# WorldClock.net
KiCad netlist of a schematic drawn in EAGLE
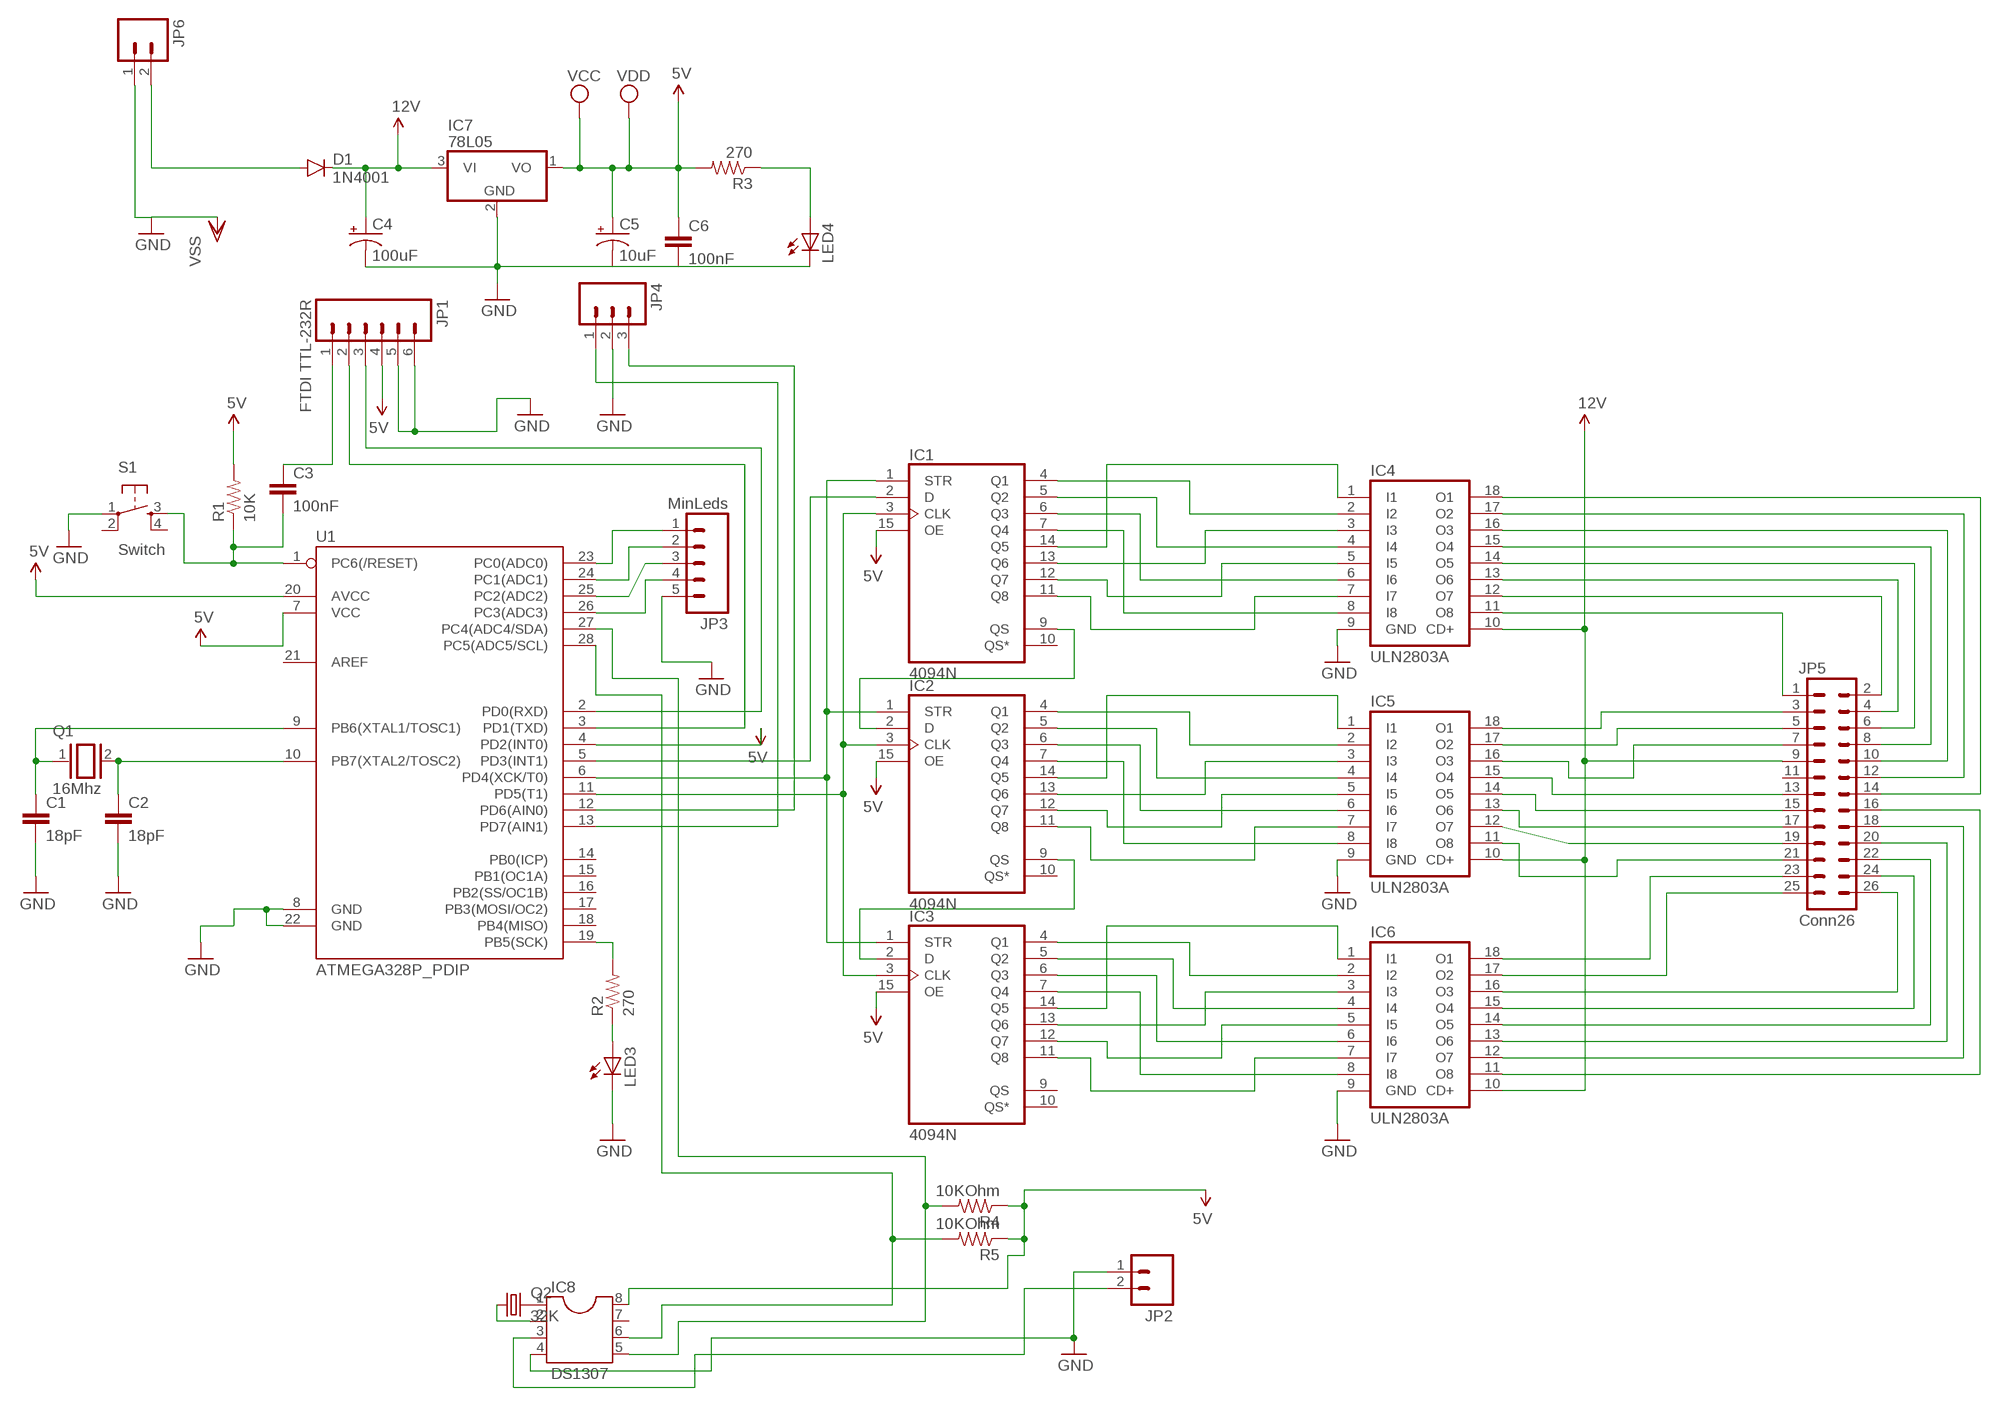
[diagram p0: schematic, sheet 1]

(export (version "E")
  (design (tool "Eeschema 10.0.6"))
  (components
    (comp (ref "C1")
      (value "18pF")
      (footprint "eagle-import:CAP-PTH-SMALL2")
      (libsource (lib "eagle-import") (part "CAPPTH2"))
    )
    (comp (ref "C2")
      (value "18pF")
      (footprint "eagle-import:CAP-PTH-SMALL2")
      (libsource (lib "eagle-import") (part "CAPPTH2"))
    )
    (comp (ref "C3")
      (value "100nF")
      (footprint "eagle-import:CAP-PTH-SMALL2")
      (libsource (lib "eagle-import") (part "CAPPTH2"))
    )
    (comp (ref "C4")
      (value "100uF")
      (footprint "eagle-import:CPOL-RADIAL-100UF-25V")
      (libsource (lib "eagle-import") (part "CAP_POLPTH1"))
    )
    (comp (ref "C5")
      (value "10uF")
      (footprint "eagle-import:CPOL-RADIAL-10UF-25V")
      (libsource (lib "eagle-import") (part "CAP_POLPTH2"))
    )
    (comp (ref "C6")
      (value "100nF")
      (footprint "eagle-import:CAP-PTH-SMALL2")
      (libsource (lib "eagle-import") (part "CAPPTH2"))
    )
    (comp (ref "D1")
      (value "1N4001")
      (footprint "eagle-import:DIODE-1N4148")
      (libsource (lib "eagle-import") (part "DIODE1N4148"))
    )
    (comp (ref "IC1")
      (value "4094N")
      (footprint "eagle-import:DIL16")
      (libsource (lib "eagle-import") (part "4094N"))
    )
    (comp (ref "IC2")
      (value "4094N")
      (footprint "eagle-import:DIL16")
      (libsource (lib "eagle-import") (part "4094N"))
    )
    (comp (ref "IC3")
      (value "4094N")
      (footprint "eagle-import:DIL16")
      (libsource (lib "eagle-import") (part "4094N"))
    )
    (comp (ref "IC4")
      (value "ULN2803A")
      (footprint "eagle-import:DIL18")
      (libsource (lib "eagle-import") (part "ULN2803A"))
    )
    (comp (ref "IC5")
      (value "ULN2803A")
      (footprint "eagle-import:DIL18")
      (libsource (lib "eagle-import") (part "ULN2803A"))
    )
    (comp (ref "IC6")
      (value "ULN2803A")
      (footprint "eagle-import:DIL18")
      (libsource (lib "eagle-import") (part "ULN2803A"))
    )
    (comp (ref "IC7")
      (value "78L05")
      (footprint "eagle-import:TO92")
      (libsource (lib "eagle-import") (part "78ZL12"))
    )
    (comp (ref "IC8")
      (value "DS1307")
      (footprint "eagle-import:SOCKET-08")
      (libsource (lib "eagle-import") (part "DIL8S"))
    )
    (comp (ref "JP1")
      (value "FTDI TTL-232R")
      (footprint "eagle-import:1X06_NO_SILK")
      (libsource (lib "eagle-import") (part "M06NO_SILK_FEMALE_PTH"))
    )
    (comp (ref "JP2")
      (value "M025MM")
      (footprint "eagle-import:SCREWTERMINAL-5MM-2")
      (libsource (lib "eagle-import") (part "M025MM"))
    )
    (comp (ref "JP3")
      (value "MinLeds")
      (footprint "eagle-import:1X05")
      (libsource (lib "eagle-import") (part "M05PTH"))
    )
    (comp (ref "JP4")
      (value "M03-SCREW-5MM")
      (footprint "eagle-import:SCREWTERMINAL-5MM-3")
      (libsource (lib "eagle-import") (part "M03-SCREW-5MM"))
    )
    (comp (ref "JP5")
      (value "Conn26")
      (footprint "eagle-import:2X13")
      (libsource (lib "eagle-import") (part "M13X22X13"))
    )
    (comp (ref "JP6")
      (value "M025MM")
      (footprint "eagle-import:SCREWTERMINAL-5MM-2")
      (libsource (lib "eagle-import") (part "M025MM"))
    )
    (comp (ref "LED3")
      (value "LED5MM")
      (footprint "eagle-import:LED5MM")
      (libsource (lib "eagle-import") (part "LED5MM"))
    )
    (comp (ref "LED4")
      (value "LED5MM")
      (footprint "eagle-import:LED5MM")
      (libsource (lib "eagle-import") (part "LED5MM"))
    )
    (comp (ref "Q1")
      (value "16Mhz")
      (footprint "eagle-import:QS")
      (libsource (lib "eagle-import") (part "XTAL/S"))
    )
    (comp (ref "Q2")
      (value "32K")
      (footprint "eagle-import:TC26V")
      (libsource (lib "eagle-import") (part "CRYSTALTC26V"))
    )
    (comp (ref "R1")
      (value "10K")
      (footprint "eagle-import:AXIAL-0.4")
      (libsource (lib "eagle-import") (part "RESISTORPTH-1/4W"))
    )
    (comp (ref "R2")
      (value "270")
      (footprint "eagle-import:AXIAL-0.4")
      (libsource (lib "eagle-import") (part "RESISTORPTH-1/4W"))
    )
    (comp (ref "R3")
      (value "270")
      (footprint "eagle-import:AXIAL-0.4")
      (libsource (lib "eagle-import") (part "RESISTORPTH-1/4W"))
    )
    (comp (ref "R4")
      (value "10KOhm")
      (footprint "eagle-import:AXIAL-0.4")
      (libsource (lib "eagle-import") (part "RESISTORPTH-1/4W"))
    )
    (comp (ref "R5")
      (value "10KOhm")
      (footprint "eagle-import:AXIAL-0.4")
      (libsource (lib "eagle-import") (part "RESISTORPTH-1/4W"))
    )
    (comp (ref "S1")
      (value "Switch")
      (footprint "eagle-import:TACTILE-PTH")
      (libsource (lib "eagle-import") (part "TAC_SWITCHPTH"))
    )
    (comp (ref "U1")
      (value "ATMEGA328P_PDIP")
      (footprint "eagle-import:DIL28-3")
      (libsource (lib "eagle-import") (part "ATMEGA328P_PDIP"))
    )
  )
  (nets
    (net (code "1") (name "5V") (class "Default")
      (node (ref "C5") (pin "1") (pinfunction "+_1") (pintype "passive"))
      (node (ref "C6") (pin "1") (pinfunction "1_1") (pintype "passive"))
      (node (ref "IC1") (pin "15") (pinfunction "OE_15") (pintype "input"))
      (node (ref "IC2") (pin "15") (pinfunction "OE_15") (pintype "input"))
      (node (ref "IC3") (pin "15") (pinfunction "OE_15") (pintype "input"))
      (node (ref "IC7") (pin "1") (pinfunction "VO_1") (pintype "passive"))
      (node (ref "IC8") (pin "8") (pinfunction "8_8") (pintype "passive"))
      (node (ref "JP1") (pin "4") (pinfunction "4_4") (pintype "passive"))
      (node (ref "R1") (pin "P$2") (pinfunction "2_P$2") (pintype "passive"))
      (node (ref "R3") (pin "P$2") (pinfunction "2_P$2") (pintype "passive"))
      (node (ref "R4") (pin "P$1") (pinfunction "1_P$1") (pintype "passive"))
      (node (ref "R5") (pin "P$1") (pinfunction "1_P$1") (pintype "passive"))
      (node (ref "U1") (pin "20") (pinfunction "AVCC_20") (pintype "bidirectional"))
      (node (ref "U1") (pin "4") (pinfunction "PD2(INT0)_4") (pintype "bidirectional"))
      (node (ref "U1") (pin "7") (pinfunction "VCC_7") (pintype "bidirectional"))
    )
    (net (code "2") (name "12V") (class "Default")
      (node (ref "C4") (pin "1") (pinfunction "+_1") (pintype "passive"))
      (node (ref "D1") (pin "C") (pinfunction "C_C") (pintype "passive"))
      (node (ref "IC4") (pin "10") (pinfunction "CD+_10") (pintype "passive"))
      (node (ref "IC5") (pin "10") (pinfunction "CD+_10") (pintype "passive"))
      (node (ref "IC6") (pin "10") (pinfunction "CD+_10") (pintype "passive"))
      (node (ref "IC7") (pin "3") (pinfunction "VI_3") (pintype "input"))
      (node (ref "JP5") (pin "9") (pinfunction "9_9") (pintype "passive"))
    )
    (net (code "3") (name "GND") (class "Default")
      (node (ref "C1") (pin "2") (pinfunction "2_2") (pintype "passive"))
      (node (ref "C2") (pin "2") (pinfunction "2_2") (pintype "passive"))
      (node (ref "C4") (pin "2") (pinfunction "-_2") (pintype "passive"))
      (node (ref "C5") (pin "2") (pinfunction "-_2") (pintype "passive"))
      (node (ref "C6") (pin "2") (pinfunction "2_2") (pintype "passive"))
      (node (ref "IC4") (pin "9") (pinfunction "GND_9") (pintype "power_in"))
      (node (ref "IC5") (pin "9") (pinfunction "GND_9") (pintype "power_in"))
      (node (ref "IC6") (pin "9") (pinfunction "GND_9") (pintype "power_in"))
      (node (ref "IC7") (pin "2") (pinfunction "GND_2") (pintype "passive"))
      (node (ref "IC8") (pin "4") (pinfunction "4_4") (pintype "passive"))
      (node (ref "JP1") (pin "5") (pinfunction "5_5") (pintype "passive"))
      (node (ref "JP1") (pin "6") (pinfunction "6_6") (pintype "passive"))
      (node (ref "JP2") (pin "1") (pinfunction "1_1") (pintype "passive"))
      (node (ref "JP3") (pin "5") (pinfunction "5_5") (pintype "passive"))
      (node (ref "JP4") (pin "2") (pinfunction "2_2") (pintype "passive"))
      (node (ref "JP6") (pin "1") (pinfunction "1_1") (pintype "passive"))
      (node (ref "LED3") (pin "K") (pinfunction "C_K") (pintype "passive"))
      (node (ref "LED4") (pin "K") (pinfunction "C_K") (pintype "passive"))
      (node (ref "S1") (pin "1") (pinfunction "1_1") (pintype "passive"))
      (node (ref "U1") (pin "22") (pinfunction "GND_22") (pintype "bidirectional"))
      (node (ref "U1") (pin "8") (pinfunction "GND_8") (pintype "bidirectional"))
    )
    (net (code "4") (name "Net-(C3-Pad1)") (class "Default")
      (node (ref "C3") (pin "1") (pinfunction "1_1") (pintype "passive"))
      (node (ref "JP1") (pin "1") (pinfunction "1_1") (pintype "passive"))
    )
    (net (code "5") (name "Net-(D1-PadA)") (class "Default")
      (node (ref "D1") (pin "A") (pinfunction "A_A") (pintype "passive"))
      (node (ref "JP6") (pin "2") (pinfunction "2_2") (pintype "passive"))
    )
    (net (code "6") (name "Net-(IC1A-CLK)") (class "Default")
      (node (ref "IC1") (pin "3") (pinfunction "CLK_3") (pintype "input"))
      (node (ref "IC2") (pin "3") (pinfunction "CLK_3") (pintype "input"))
      (node (ref "IC3") (pin "3") (pinfunction "CLK_3") (pintype "input"))
      (node (ref "U1") (pin "11") (pinfunction "PD5(T1)_11") (pintype "bidirectional"))
    )
    (net (code "7") (name "Net-(IC1A-D)") (class "Default")
      (node (ref "IC1") (pin "2") (pinfunction "D_2") (pintype "input"))
      (node (ref "U1") (pin "5") (pinfunction "PD3(INT1)_5") (pintype "bidirectional"))
    )
    (net (code "8") (name "Net-(IC1A-Q1)") (class "Default")
      (node (ref "IC1") (pin "4") (pinfunction "Q1_4") (pintype "output"))
      (node (ref "IC4") (pin "2") (pinfunction "I2_2") (pintype "input"))
    )
    (net (code "9") (name "Net-(IC1A-Q2)") (class "Default")
      (node (ref "IC1") (pin "5") (pinfunction "Q2_5") (pintype "output"))
      (node (ref "IC4") (pin "4") (pinfunction "I4_4") (pintype "input"))
    )
    (net (code "10") (name "Net-(IC1A-Q3)") (class "Default")
      (node (ref "IC1") (pin "6") (pinfunction "Q3_6") (pintype "output"))
      (node (ref "IC4") (pin "6") (pinfunction "I6_6") (pintype "input"))
    )
    (net (code "11") (name "Net-(IC1A-Q4)") (class "Default")
      (node (ref "IC1") (pin "7") (pinfunction "Q4_7") (pintype "output"))
      (node (ref "IC4") (pin "8") (pinfunction "I8_8") (pintype "input"))
    )
    (net (code "12") (name "Net-(IC1A-Q5)") (class "Default")
      (node (ref "IC1") (pin "14") (pinfunction "Q5_14") (pintype "output"))
      (node (ref "IC4") (pin "1") (pinfunction "I1_1") (pintype "input"))
    )
    (net (code "13") (name "Net-(IC1A-Q6)") (class "Default")
      (node (ref "IC1") (pin "13") (pinfunction "Q6_13") (pintype "output"))
      (node (ref "IC4") (pin "3") (pinfunction "I3_3") (pintype "input"))
    )
    (net (code "14") (name "Net-(IC1A-Q7)") (class "Default")
      (node (ref "IC1") (pin "12") (pinfunction "Q7_12") (pintype "output"))
      (node (ref "IC4") (pin "5") (pinfunction "I5_5") (pintype "input"))
    )
    (net (code "15") (name "Net-(IC1A-Q8)") (class "Default")
      (node (ref "IC1") (pin "11") (pinfunction "Q8_11") (pintype "output"))
      (node (ref "IC4") (pin "7") (pinfunction "I7_7") (pintype "input"))
    )
    (net (code "16") (name "Net-(IC1A-QS)") (class "Default")
      (node (ref "IC1") (pin "9") (pinfunction "QS_9") (pintype "output"))
      (node (ref "IC2") (pin "2") (pinfunction "D_2") (pintype "input"))
    )
    (net (code "17") (name "Net-(IC1A-STR)") (class "Default")
      (node (ref "IC1") (pin "1") (pinfunction "STR_1") (pintype "input"))
      (node (ref "IC2") (pin "1") (pinfunction "STR_1") (pintype "input"))
      (node (ref "IC3") (pin "1") (pinfunction "STR_1") (pintype "input"))
      (node (ref "U1") (pin "6") (pinfunction "PD4(XCK/T0)_6") (pintype "bidirectional"))
    )
    (net (code "18") (name "Net-(IC2A-Q1)") (class "Default")
      (node (ref "IC2") (pin "4") (pinfunction "Q1_4") (pintype "output"))
      (node (ref "IC5") (pin "2") (pinfunction "I2_2") (pintype "input"))
    )
    (net (code "19") (name "Net-(IC2A-Q2)") (class "Default")
      (node (ref "IC2") (pin "5") (pinfunction "Q2_5") (pintype "output"))
      (node (ref "IC5") (pin "4") (pinfunction "I4_4") (pintype "input"))
    )
    (net (code "20") (name "Net-(IC2A-Q3)") (class "Default")
      (node (ref "IC2") (pin "6") (pinfunction "Q3_6") (pintype "output"))
      (node (ref "IC5") (pin "6") (pinfunction "I6_6") (pintype "input"))
    )
    (net (code "21") (name "Net-(IC2A-Q4)") (class "Default")
      (node (ref "IC2") (pin "7") (pinfunction "Q4_7") (pintype "output"))
      (node (ref "IC5") (pin "8") (pinfunction "I8_8") (pintype "input"))
    )
    (net (code "22") (name "Net-(IC2A-Q5)") (class "Default")
      (node (ref "IC2") (pin "14") (pinfunction "Q5_14") (pintype "output"))
      (node (ref "IC5") (pin "1") (pinfunction "I1_1") (pintype "input"))
    )
    (net (code "23") (name "Net-(IC2A-Q6)") (class "Default")
      (node (ref "IC2") (pin "13") (pinfunction "Q6_13") (pintype "output"))
      (node (ref "IC5") (pin "3") (pinfunction "I3_3") (pintype "input"))
    )
    (net (code "24") (name "Net-(IC2A-Q7)") (class "Default")
      (node (ref "IC2") (pin "12") (pinfunction "Q7_12") (pintype "output"))
      (node (ref "IC5") (pin "5") (pinfunction "I5_5") (pintype "input"))
    )
    (net (code "25") (name "Net-(IC2A-Q8)") (class "Default")
      (node (ref "IC2") (pin "11") (pinfunction "Q8_11") (pintype "output"))
      (node (ref "IC5") (pin "7") (pinfunction "I7_7") (pintype "input"))
    )
    (net (code "26") (name "Net-(IC2A-QS)") (class "Default")
      (node (ref "IC2") (pin "9") (pinfunction "QS_9") (pintype "output"))
      (node (ref "IC3") (pin "2") (pinfunction "D_2") (pintype "input"))
    )
    (net (code "27") (name "Net-(IC3A-Q1)") (class "Default")
      (node (ref "IC3") (pin "4") (pinfunction "Q1_4") (pintype "output"))
      (node (ref "IC6") (pin "2") (pinfunction "I2_2") (pintype "input"))
    )
    (net (code "28") (name "Net-(IC3A-Q2)") (class "Default")
      (node (ref "IC3") (pin "5") (pinfunction "Q2_5") (pintype "output"))
      (node (ref "IC6") (pin "4") (pinfunction "I4_4") (pintype "input"))
    )
    (net (code "29") (name "Net-(IC3A-Q3)") (class "Default")
      (node (ref "IC3") (pin "6") (pinfunction "Q3_6") (pintype "output"))
      (node (ref "IC6") (pin "6") (pinfunction "I6_6") (pintype "input"))
    )
    (net (code "30") (name "Net-(IC3A-Q4)") (class "Default")
      (node (ref "IC3") (pin "7") (pinfunction "Q4_7") (pintype "output"))
      (node (ref "IC6") (pin "8") (pinfunction "I8_8") (pintype "input"))
    )
    (net (code "31") (name "Net-(IC3A-Q5)") (class "Default")
      (node (ref "IC3") (pin "14") (pinfunction "Q5_14") (pintype "output"))
      (node (ref "IC6") (pin "1") (pinfunction "I1_1") (pintype "input"))
    )
    (net (code "32") (name "Net-(IC3A-Q6)") (class "Default")
      (node (ref "IC3") (pin "13") (pinfunction "Q6_13") (pintype "output"))
      (node (ref "IC6") (pin "3") (pinfunction "I3_3") (pintype "input"))
    )
    (net (code "33") (name "Net-(IC3A-Q7)") (class "Default")
      (node (ref "IC3") (pin "12") (pinfunction "Q7_12") (pintype "output"))
      (node (ref "IC6") (pin "5") (pinfunction "I5_5") (pintype "input"))
    )
    (net (code "34") (name "Net-(IC3A-Q8)") (class "Default")
      (node (ref "IC3") (pin "11") (pinfunction "Q8_11") (pintype "output"))
      (node (ref "IC6") (pin "7") (pinfunction "I7_7") (pintype "input"))
    )
    (net (code "35") (name "Net-(IC4-O1)") (class "Default")
      (node (ref "IC4") (pin "18") (pinfunction "O1_18") (pintype "open_collector"))
      (node (ref "JP5") (pin "14") (pinfunction "14_14") (pintype "passive"))
    )
    (net (code "36") (name "Net-(IC4-O2)") (class "Default")
      (node (ref "IC4") (pin "17") (pinfunction "O2_17") (pintype "open_collector"))
      (node (ref "JP5") (pin "12") (pinfunction "12_12") (pintype "passive"))
    )
    (net (code "37") (name "Net-(IC4-O3)") (class "Default")
      (node (ref "IC4") (pin "16") (pinfunction "O3_16") (pintype "open_collector"))
      (node (ref "JP5") (pin "10") (pinfunction "10_10") (pintype "passive"))
    )
    (net (code "38") (name "Net-(IC4-O4)") (class "Default")
      (node (ref "IC4") (pin "15") (pinfunction "O4_15") (pintype "open_collector"))
      (node (ref "JP5") (pin "8") (pinfunction "8_8") (pintype "passive"))
    )
    (net (code "39") (name "Net-(IC4-O5)") (class "Default")
      (node (ref "IC4") (pin "14") (pinfunction "O5_14") (pintype "open_collector"))
      (node (ref "JP5") (pin "6") (pinfunction "6_6") (pintype "passive"))
    )
    (net (code "40") (name "Net-(IC4-O6)") (class "Default")
      (node (ref "IC4") (pin "13") (pinfunction "O6_13") (pintype "open_collector"))
      (node (ref "JP5") (pin "4") (pinfunction "4_4") (pintype "passive"))
    )
    (net (code "41") (name "Net-(IC4-O7)") (class "Default")
      (node (ref "IC4") (pin "12") (pinfunction "O7_12") (pintype "open_collector"))
      (node (ref "JP5") (pin "2") (pinfunction "2_2") (pintype "passive"))
    )
    (net (code "42") (name "Net-(IC4-O8)") (class "Default")
      (node (ref "IC4") (pin "11") (pinfunction "O8_11") (pintype "open_collector"))
      (node (ref "JP5") (pin "1") (pinfunction "1_1") (pintype "passive"))
    )
    (net (code "43") (name "Net-(IC5-O1)") (class "Default")
      (node (ref "IC5") (pin "18") (pinfunction "O1_18") (pintype "open_collector"))
      (node (ref "JP5") (pin "3") (pinfunction "3_3") (pintype "passive"))
    )
    (net (code "44") (name "Net-(IC5-O2)") (class "Default")
      (node (ref "IC5") (pin "17") (pinfunction "O2_17") (pintype "open_collector"))
      (node (ref "JP5") (pin "5") (pinfunction "5_5") (pintype "passive"))
    )
    (net (code "45") (name "Net-(IC5-O3)") (class "Default")
      (node (ref "IC5") (pin "16") (pinfunction "O3_16") (pintype "open_collector"))
      (node (ref "JP5") (pin "7") (pinfunction "7_7") (pintype "passive"))
    )
    (net (code "46") (name "Net-(IC5-O4)") (class "Default")
      (node (ref "IC5") (pin "15") (pinfunction "O4_15") (pintype "open_collector"))
      (node (ref "JP5") (pin "13") (pinfunction "13_13") (pintype "passive"))
    )
    (net (code "47") (name "Net-(IC5-O5)") (class "Default")
      (node (ref "IC5") (pin "14") (pinfunction "O5_14") (pintype "open_collector"))
      (node (ref "JP5") (pin "15") (pinfunction "15_15") (pintype "passive"))
    )
    (net (code "48") (name "Net-(IC5-O6)") (class "Default")
      (node (ref "IC5") (pin "13") (pinfunction "O6_13") (pintype "open_collector"))
      (node (ref "JP5") (pin "17") (pinfunction "17_17") (pintype "passive"))
    )
    (net (code "49") (name "Net-(IC5-O7)") (class "Default")
      (node (ref "IC5") (pin "12") (pinfunction "O7_12") (pintype "open_collector"))
      (node (ref "JP5") (pin "19") (pinfunction "19_19") (pintype "passive"))
    )
    (net (code "50") (name "Net-(IC5-O8)") (class "Default")
      (node (ref "IC5") (pin "11") (pinfunction "O8_11") (pintype "open_collector"))
      (node (ref "JP5") (pin "21") (pinfunction "21_21") (pintype "passive"))
    )
    (net (code "51") (name "Net-(IC6-O1)") (class "Default")
      (node (ref "IC6") (pin "18") (pinfunction "O1_18") (pintype "open_collector"))
      (node (ref "JP5") (pin "23") (pinfunction "23_23") (pintype "passive"))
    )
    (net (code "52") (name "Net-(IC6-O2)") (class "Default")
      (node (ref "IC6") (pin "17") (pinfunction "O2_17") (pintype "open_collector"))
      (node (ref "JP5") (pin "25") (pinfunction "25_25") (pintype "passive"))
    )
    (net (code "53") (name "Net-(IC6-O3)") (class "Default")
      (node (ref "IC6") (pin "16") (pinfunction "O3_16") (pintype "open_collector"))
      (node (ref "JP5") (pin "26") (pinfunction "26_26") (pintype "passive"))
    )
    (net (code "54") (name "Net-(IC6-O4)") (class "Default")
      (node (ref "IC6") (pin "15") (pinfunction "O4_15") (pintype "open_collector"))
      (node (ref "JP5") (pin "24") (pinfunction "24_24") (pintype "passive"))
    )
    (net (code "55") (name "Net-(IC6-O5)") (class "Default")
      (node (ref "IC6") (pin "14") (pinfunction "O5_14") (pintype "open_collector"))
      (node (ref "JP5") (pin "22") (pinfunction "22_22") (pintype "passive"))
    )
    (net (code "56") (name "Net-(IC6-O6)") (class "Default")
      (node (ref "IC6") (pin "13") (pinfunction "O6_13") (pintype "open_collector"))
      (node (ref "JP5") (pin "20") (pinfunction "20_20") (pintype "passive"))
    )
    (net (code "57") (name "Net-(IC6-O7)") (class "Default")
      (node (ref "IC6") (pin "12") (pinfunction "O7_12") (pintype "open_collector"))
      (node (ref "JP5") (pin "18") (pinfunction "18_18") (pintype "passive"))
    )
    (net (code "58") (name "Net-(IC6-O8)") (class "Default")
      (node (ref "IC6") (pin "11") (pinfunction "O8_11") (pintype "open_collector"))
      (node (ref "JP5") (pin "16") (pinfunction "16_16") (pintype "passive"))
    )
    (net (code "59") (name "Net-(IC8-Pad1)") (class "Default")
      (node (ref "IC8") (pin "1") (pinfunction "1_1") (pintype "passive"))
      (node (ref "Q2") (pin "2") (pinfunction "2_2") (pintype "passive"))
    )
    (net (code "60") (name "Net-(IC8-Pad2)") (class "Default")
      (node (ref "IC8") (pin "2") (pinfunction "2_2") (pintype "passive"))
      (node (ref "Q2") (pin "1") (pinfunction "1_1") (pintype "passive"))
    )
    (net (code "61") (name "Net-(IC8-Pad3)") (class "Default")
      (node (ref "IC8") (pin "3") (pinfunction "3_3") (pintype "passive"))
      (node (ref "JP2") (pin "2") (pinfunction "2_2") (pintype "passive"))
    )
    (net (code "62") (name "Net-(R1-1)") (class "Default")
      (node (ref "C3") (pin "2") (pinfunction "2_2") (pintype "passive"))
      (node (ref "R1") (pin "P$1") (pinfunction "1_P$1") (pintype "passive"))
      (node (ref "S1") (pin "3") (pinfunction "3_3") (pintype "passive"))
      (node (ref "U1") (pin "1") (pinfunction "PC6(/RESET)_1") (pintype "bidirectional"))
    )
    (net (code "63") (name "Net-(R2-1)") (class "Default")
      (node (ref "LED3") (pin "A") (pinfunction "A_A") (pintype "passive"))
      (node (ref "R2") (pin "P$1") (pinfunction "1_P$1") (pintype "passive"))
    )
    (net (code "64") (name "Net-(R2-2)") (class "Default")
      (node (ref "R2") (pin "P$2") (pinfunction "2_P$2") (pintype "passive"))
      (node (ref "U1") (pin "19") (pinfunction "PB5(SCK)_19") (pintype "bidirectional"))
    )
    (net (code "65") (name "Net-(R3-1)") (class "Default")
      (node (ref "LED4") (pin "A") (pinfunction "A_A") (pintype "passive"))
      (node (ref "R3") (pin "P$1") (pinfunction "1_P$1") (pintype "passive"))
    )
    (net (code "66") (name "Net-(R4-2)") (class "Default")
      (node (ref "IC8") (pin "5") (pinfunction "5_5") (pintype "passive"))
      (node (ref "R4") (pin "P$2") (pinfunction "2_P$2") (pintype "passive"))
      (node (ref "U1") (pin "27") (pinfunction "PC4(ADC4/SDA)_27") (pintype "bidirectional"))
    )
    (net (code "67") (name "Net-(R5-2)") (class "Default")
      (node (ref "IC8") (pin "6") (pinfunction "6_6") (pintype "passive"))
      (node (ref "R5") (pin "P$2") (pinfunction "2_P$2") (pintype "passive"))
      (node (ref "U1") (pin "28") (pinfunction "PC5(ADC5/SCL)_28") (pintype "bidirectional"))
    )
    (net (code "68") (name "Net-(U1-PB6(XTAL1{slash}TOSC1))") (class "Default")
      (node (ref "C1") (pin "1") (pinfunction "1_1") (pintype "passive"))
      (node (ref "Q1") (pin "1") (pinfunction "1_1") (pintype "passive"))
      (node (ref "U1") (pin "9") (pinfunction "PB6(XTAL1/TOSC1)_9") (pintype "bidirectional"))
    )
    (net (code "69") (name "Net-(U1-PB7(XTAL2{slash}TOSC2))") (class "Default")
      (node (ref "C2") (pin "1") (pinfunction "1_1") (pintype "passive"))
      (node (ref "Q1") (pin "2") (pinfunction "2_2") (pintype "passive"))
      (node (ref "U1") (pin "10") (pinfunction "PB7(XTAL2/TOSC2)_10") (pintype "bidirectional"))
    )
    (net (code "70") (name "Net-(U1-PC0(ADC0))") (class "Default")
      (node (ref "JP3") (pin "1") (pinfunction "1_1") (pintype "passive"))
      (node (ref "U1") (pin "23") (pinfunction "PC0(ADC0)_23") (pintype "bidirectional"))
    )
    (net (code "71") (name "Net-(U1-PC1(ADC1))") (class "Default")
      (node (ref "JP3") (pin "2") (pinfunction "2_2") (pintype "passive"))
      (node (ref "U1") (pin "24") (pinfunction "PC1(ADC1)_24") (pintype "bidirectional"))
    )
    (net (code "72") (name "Net-(U1-PC2(ADC2))") (class "Default")
      (node (ref "JP3") (pin "3") (pinfunction "3_3") (pintype "passive"))
      (node (ref "U1") (pin "25") (pinfunction "PC2(ADC2)_25") (pintype "bidirectional"))
    )
    (net (code "73") (name "Net-(U1-PC3(ADC3))") (class "Default")
      (node (ref "JP3") (pin "4") (pinfunction "4_4") (pintype "passive"))
      (node (ref "U1") (pin "26") (pinfunction "PC3(ADC3)_26") (pintype "bidirectional"))
    )
    (net (code "74") (name "Net-(U1-PD0(RXD))") (class "Default")
      (node (ref "JP1") (pin "3") (pinfunction "3_3") (pintype "passive"))
      (node (ref "U1") (pin "2") (pinfunction "PD0(RXD)_2") (pintype "bidirectional"))
    )
    (net (code "75") (name "Net-(U1-PD1(TXD))") (class "Default")
      (node (ref "JP1") (pin "2") (pinfunction "2_2") (pintype "passive"))
      (node (ref "U1") (pin "3") (pinfunction "PD1(TXD)_3") (pintype "bidirectional"))
    )
    (net (code "76") (name "Net-(U1-PD6(AIN0))") (class "Default")
      (node (ref "JP4") (pin "3") (pinfunction "3_3") (pintype "passive"))
      (node (ref "U1") (pin "12") (pinfunction "PD6(AIN0)_12") (pintype "bidirectional"))
    )
    (net (code "77") (name "Net-(U1-PD7(AIN1))") (class "Default")
      (node (ref "JP4") (pin "1") (pinfunction "1_1") (pintype "passive"))
      (node (ref "U1") (pin "13") (pinfunction "PD7(AIN1)_13") (pintype "bidirectional"))
    )
    (net (code "78") (name "unconnected-(IC1A-QS*-Pad10)") (class "Default")
      (node (ref "IC1") (pin "10") (pinfunction "QS*_10") (pintype "output"))
    )
    (net (code "79") (name "unconnected-(IC2A-QS*-Pad10)") (class "Default")
      (node (ref "IC2") (pin "10") (pinfunction "QS*_10") (pintype "output"))
    )
    (net (code "80") (name "unconnected-(IC3A-QS*-Pad10)") (class "Default")
      (node (ref "IC3") (pin "10") (pinfunction "QS*_10") (pintype "output"))
    )
    (net (code "81") (name "unconnected-(IC3A-QS-Pad9)") (class "Default")
      (node (ref "IC3") (pin "9") (pinfunction "QS_9") (pintype "output"))
    )
    (net (code "82") (name "unconnected-(IC8-Pad7)") (class "Default")
      (node (ref "IC8") (pin "7") (pinfunction "7_7") (pintype "passive"))
    )
    (net (code "83") (name "unconnected-(JP5-Pad11)") (class "Default")
      (node (ref "JP5") (pin "11") (pinfunction "11_11") (pintype "passive"))
    )
    (net (code "84") (name "unconnected-(S1-Pad2)") (class "Default")
      (node (ref "S1") (pin "2") (pinfunction "2_2") (pintype "passive"))
    )
    (net (code "85") (name "unconnected-(S1-Pad4)") (class "Default")
      (node (ref "S1") (pin "4") (pinfunction "4_4") (pintype "passive"))
    )
    (net (code "86") (name "unconnected-(U1-AREF-Pad21)") (class "Default")
      (node (ref "U1") (pin "21") (pinfunction "AREF_21") (pintype "bidirectional"))
    )
    (net (code "87") (name "unconnected-(U1-PB0(ICP)-Pad14)") (class "Default")
      (node (ref "U1") (pin "14") (pinfunction "PB0(ICP)_14") (pintype "bidirectional"))
    )
    (net (code "88") (name "unconnected-(U1-PB1(OC1A)-Pad15)") (class "Default")
      (node (ref "U1") (pin "15") (pinfunction "PB1(OC1A)_15") (pintype "bidirectional"))
    )
    (net (code "89") (name "unconnected-(U1-PB2(SS{slash}OC1B)-Pad16)") (class "Default")
      (node (ref "U1") (pin "16") (pinfunction "PB2(SS/OC1B)_16") (pintype "bidirectional"))
    )
    (net (code "90") (name "unconnected-(U1-PB3(MOSI{slash}OC2)-Pad17)") (class "Default")
      (node (ref "U1") (pin "17") (pinfunction "PB3(MOSI/OC2)_17") (pintype "bidirectional"))
    )
    (net (code "91") (name "unconnected-(U1-PB4(MISO)-Pad18)") (class "Default")
      (node (ref "U1") (pin "18") (pinfunction "PB4(MISO)_18") (pintype "bidirectional"))
    )
  )
)
